# Sheet3.net
KiCad netlist of a schematic drawn in Altium Designer
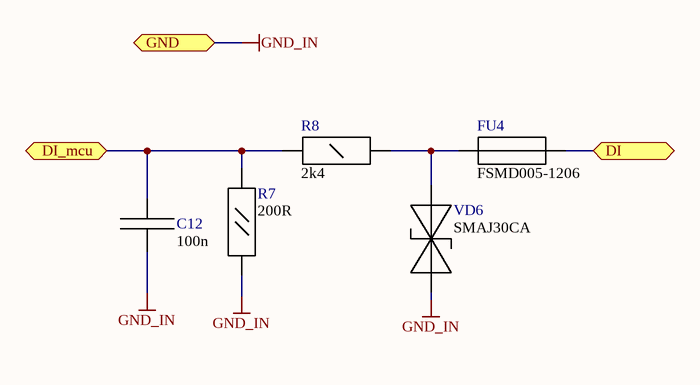
[diagram p0: Sheet3.SchDoc]

(export (version "E")
  (design (tool "Eeschema 10.0.6"))
  (components
    (comp (ref "C12")
      (value "100n")
      (footprint "Cap Ceramic 0805")
      (libsource (lib "Россыпь") (part "Capacitor Nonpolar"))
    )
    (comp (ref "FU4")
      (value "FSMD005-1206")
      (footprint "Fuse 1206")
      (libsource (lib "Россыпь") (part "FSMDxxx-1206"))
    )
    (comp (ref "R7")
      (value "200R")
      (footprint "Resistor 0805")
      (libsource (lib "Россыпь") (part "Resistor 0,125W"))
    )
    (comp (ref "R8")
      (value "2k4")
      (footprint "Resistor 1206")
      (libsource (lib "Россыпь") (part "Resistor 0,25W"))
    )
    (comp (ref "VD6")
      (value "SMAJ30CA")
      (footprint "DO-214AC SMA")
      (libsource (lib "Россыпь") (part "SMAJxxCA"))
    )
  )
  (nets
    (net (code "1") (name "/DI") (class "Default")
      (node (ref "FU4") (pin "1") (pinfunction "1_1") (pintype "passive"))
    )
    (net (code "2") (name "/DI_mcu") (class "Default")
      (node (ref "C12") (pin "1") (pinfunction "1_1") (pintype "passive"))
      (node (ref "R7") (pin "2") (pinfunction "2_2") (pintype "passive"))
      (node (ref "R8") (pin "1") (pinfunction "1_1") (pintype "passive"))
    )
    (net (code "3") (name "GND_IN") (class "Default")
      (node (ref "C12") (pin "2") (pinfunction "2_2") (pintype "passive"))
      (node (ref "R7") (pin "1") (pinfunction "1_1") (pintype "passive"))
      (node (ref "VD6") (pin "1") (pinfunction "1_1") (pintype "passive"))
    )
    (net (code "4") (name "Net-(FU4-Pad2)") (class "Default")
      (node (ref "FU4") (pin "2") (pinfunction "2_2") (pintype "passive"))
      (node (ref "R8") (pin "2") (pinfunction "2_2") (pintype "passive"))
      (node (ref "VD6") (pin "2") (pinfunction "2_2") (pintype "passive"))
    )
  )
)
